# ZeeSoC_v1_0.net
KiCad netlist of a schematic drawn in EAGLE
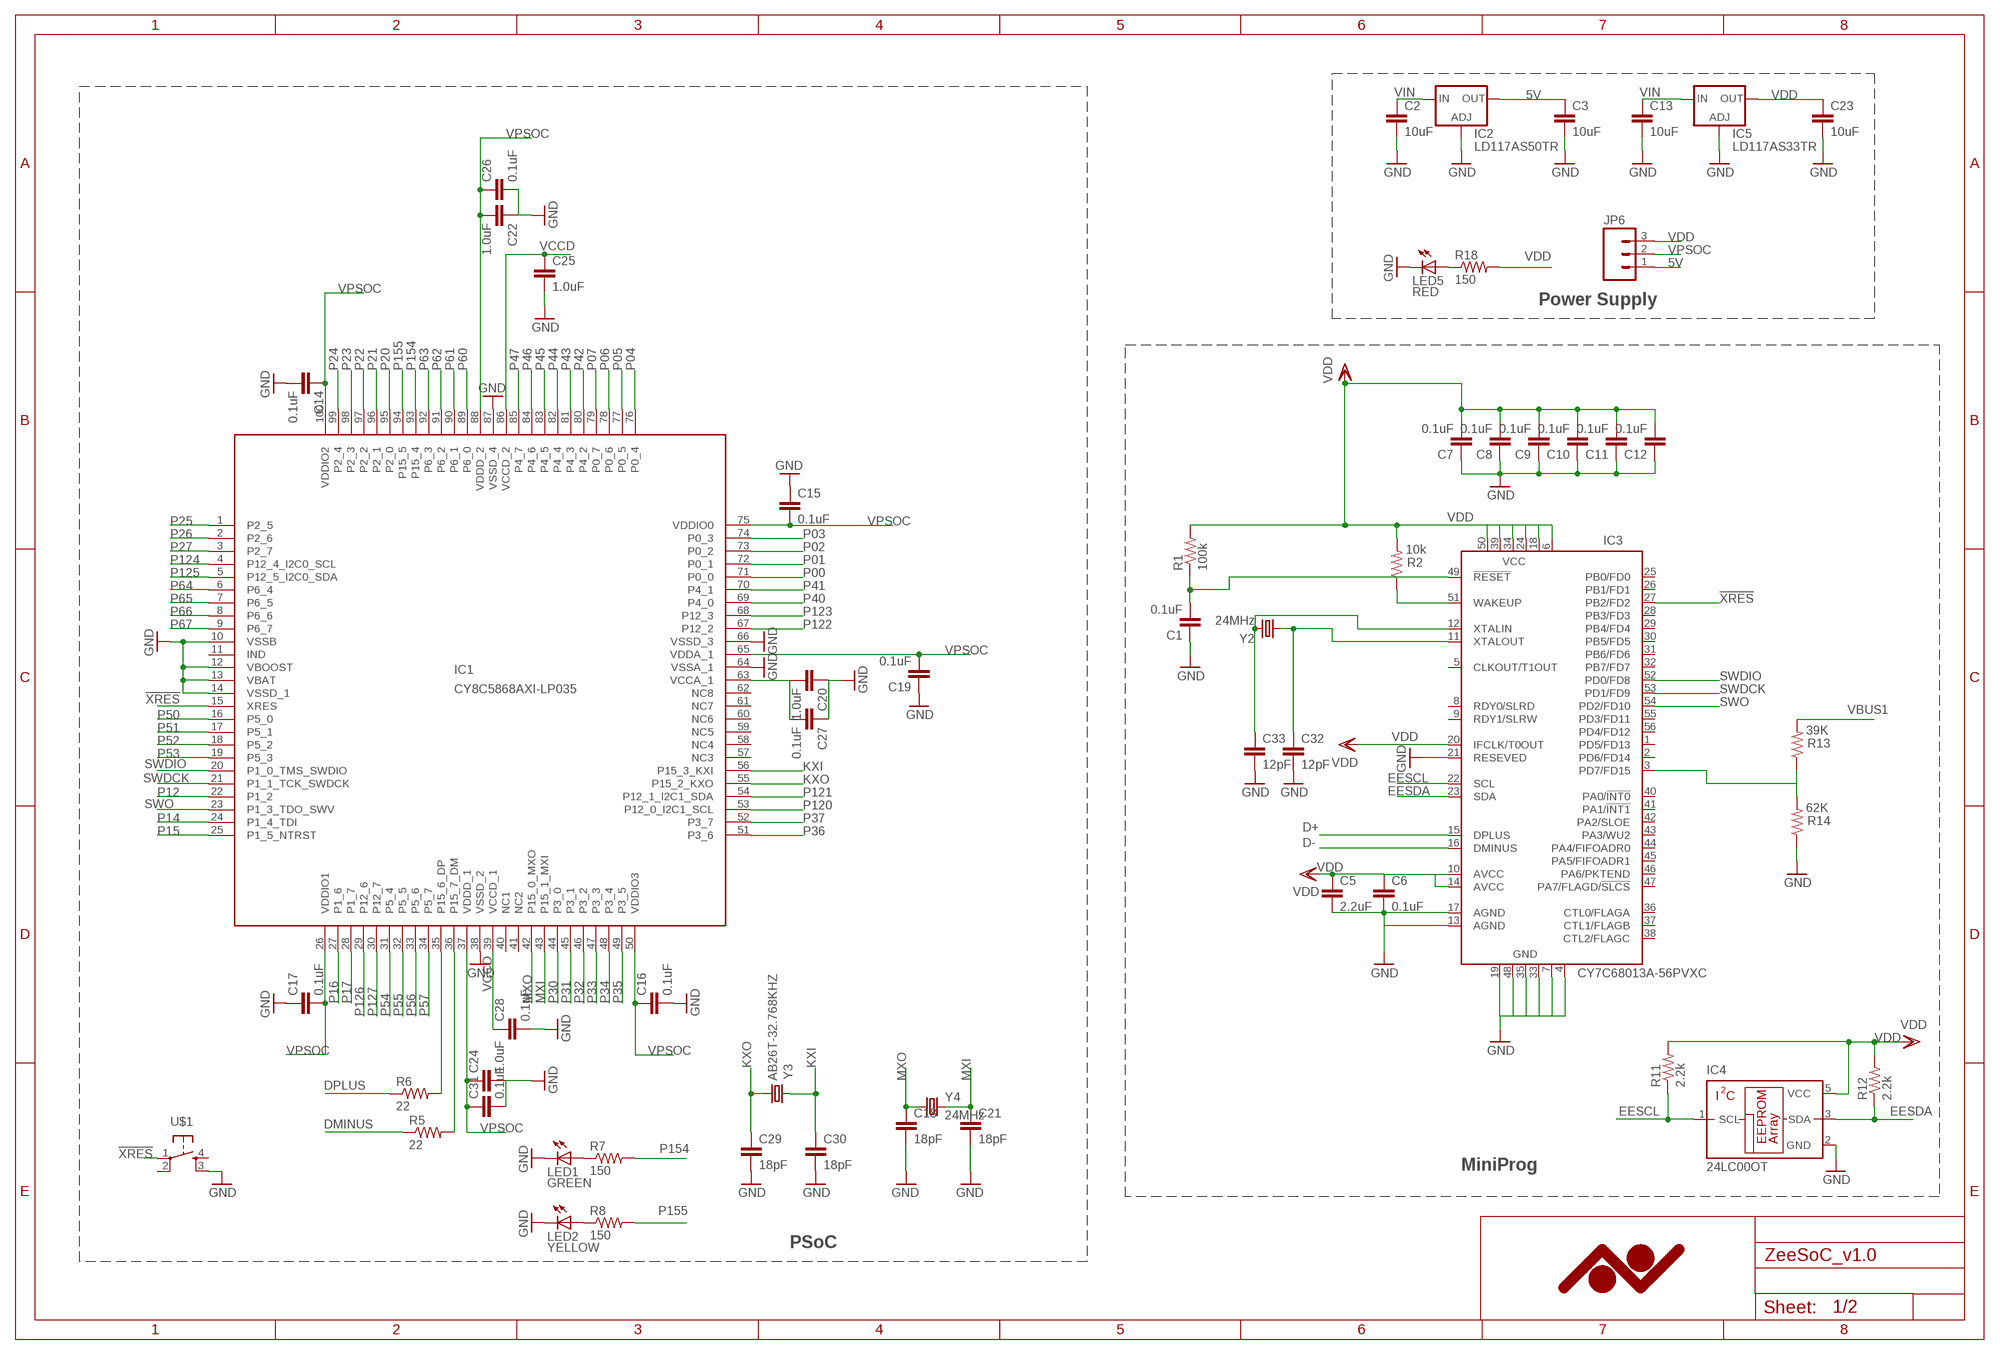
[diagram p0: schematic, sheet 1]
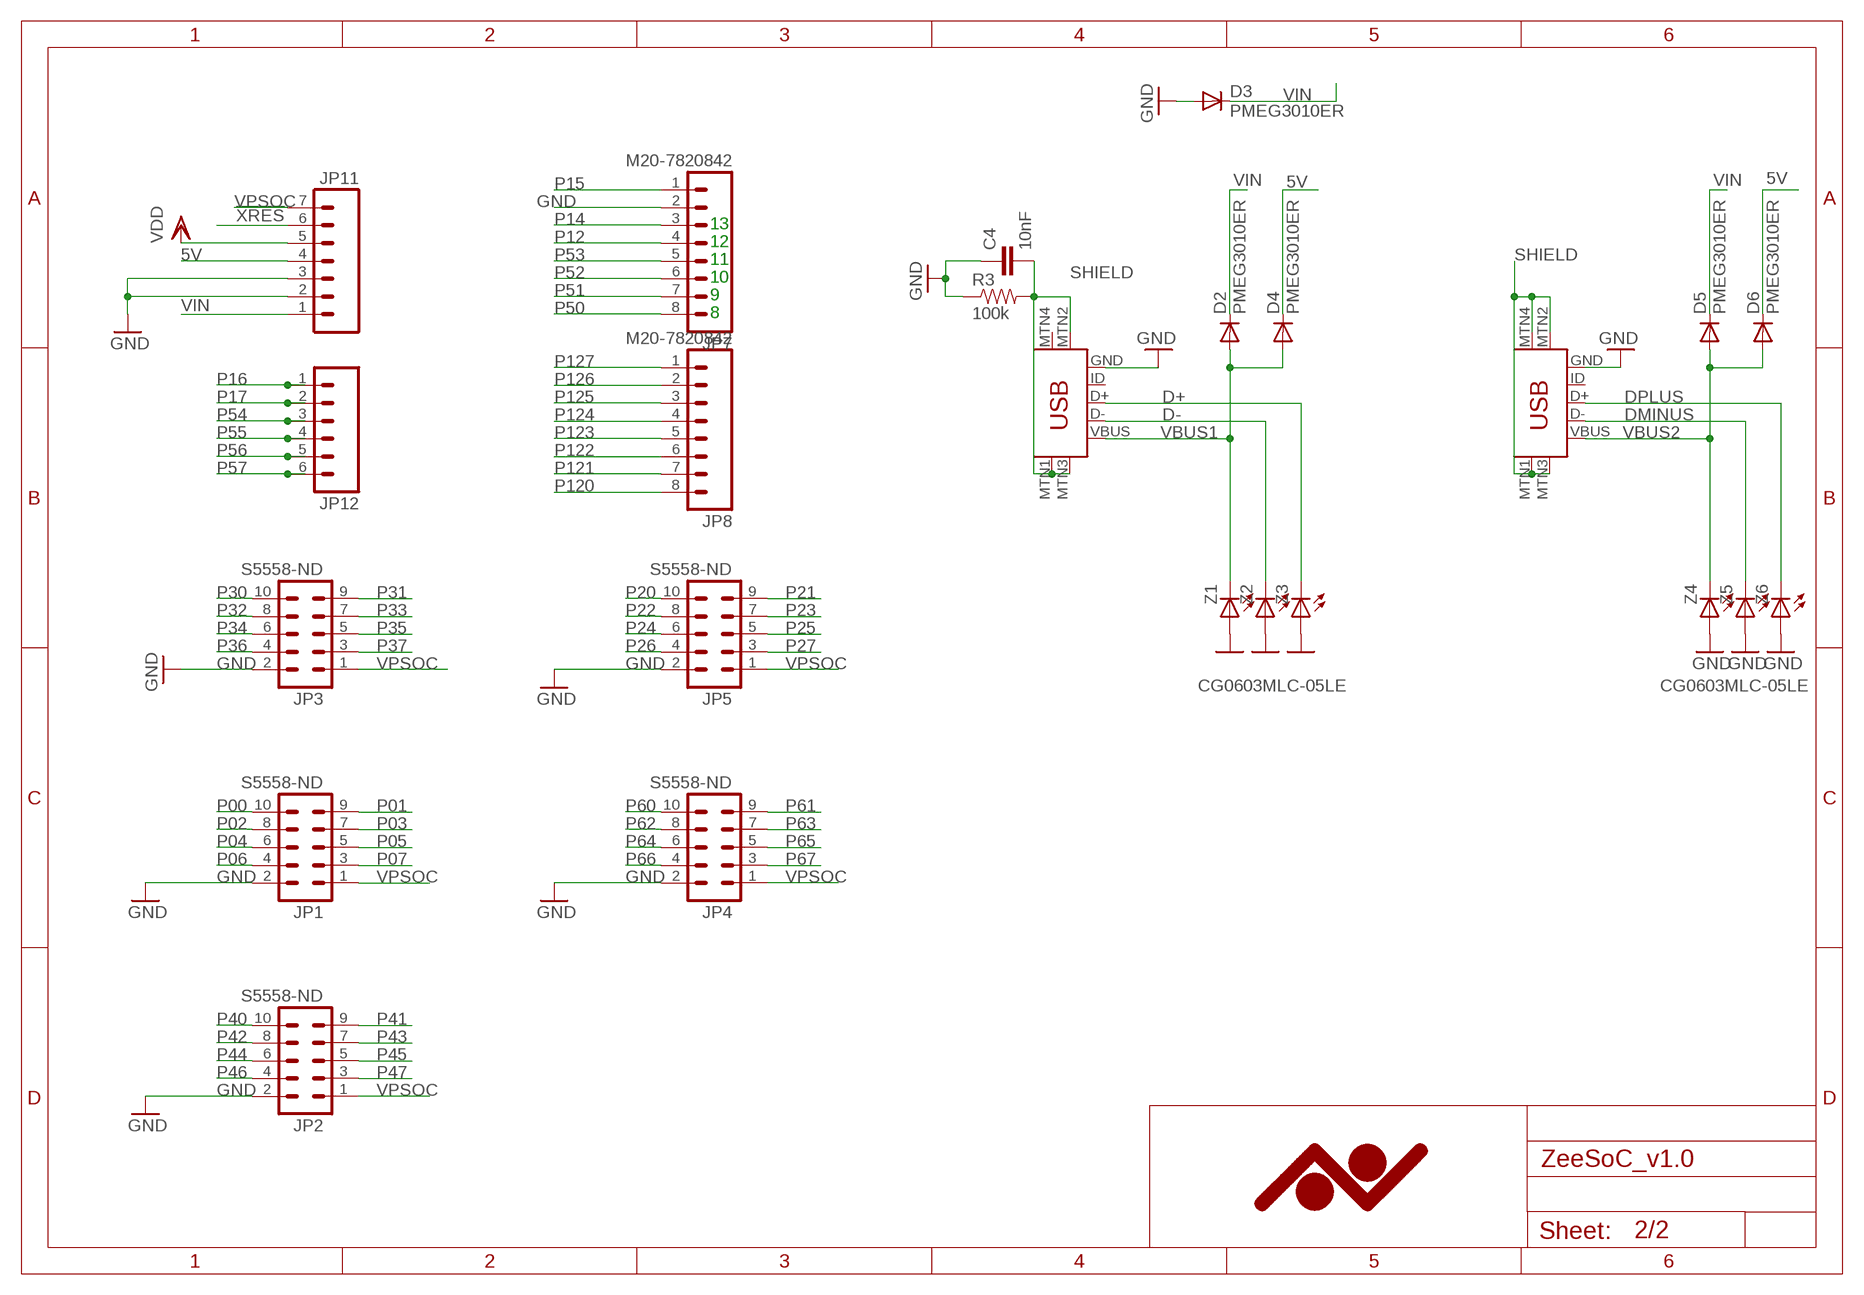
[diagram p1: schematic, sheet 2]

(export (version "E")
  (design (tool "Eeschema 10.0.6"))
  (components
    (comp (ref "C4")
      (value "10nF")
      (footprint "eagle-import:0603-CAP")
      (libsource (lib "eagle-import") (part "SparkFun-Capacitors_CAP0603-CAP"))
    )
    (comp (ref "D2")
      (value "PMEG3010ER")
      (footprint "eagle-import:SOD123")
      (libsource (lib "eagle-import") (part "DIODE-SOD123"))
    )
    (comp (ref "D3")
      (value "PMEG3010ER")
      (footprint "eagle-import:SOD123")
      (libsource (lib "eagle-import") (part "DIODE-SOD123"))
    )
    (comp (ref "D4")
      (value "PMEG3010ER")
      (footprint "eagle-import:SOD123")
      (libsource (lib "eagle-import") (part "DIODE-SOD123"))
    )
    (comp (ref "D5")
      (value "PMEG3010ER")
      (footprint "eagle-import:SOD123")
      (libsource (lib "eagle-import") (part "DIODE-SOD123"))
    )
    (comp (ref "D6")
      (value "PMEG3010ER")
      (footprint "eagle-import:SOD123")
      (libsource (lib "eagle-import") (part "DIODE-SOD123"))
    )
    (comp (ref "JP1")
      (value "S5558-ND")
      (footprint "eagle-import:2X5-NS")
      (libsource (lib "eagle-import") (part "M05X2BLANK"))
    )
    (comp (ref "JP2")
      (value "S5558-ND")
      (footprint "eagle-import:2X5-NS")
      (libsource (lib "eagle-import") (part "M05X2BLANK"))
    )
    (comp (ref "JP3")
      (value "S5558-ND")
      (footprint "eagle-import:2X5-NS")
      (libsource (lib "eagle-import") (part "M05X2BLANK"))
    )
    (comp (ref "JP4")
      (value "S5558-ND")
      (footprint "eagle-import:2X5-NS")
      (libsource (lib "eagle-import") (part "M05X2BLANK"))
    )
    (comp (ref "JP5")
      (value "S5558-ND")
      (footprint "eagle-import:2X5-NS")
      (libsource (lib "eagle-import") (part "M05X2BLANK"))
    )
    (comp (ref "JP7")
      (value "M20-7820842")
      (footprint "eagle-import:1X08")
      (libsource (lib "eagle-import") (part "M081X08"))
    )
    (comp (ref "JP8")
      (value "M20-7820842")
      (footprint "eagle-import:1X08")
      (libsource (lib "eagle-import") (part "M081X08"))
    )
    (comp (ref "JP11")
      (value "M07")
      (footprint "eagle-import:1X07")
      (libsource (lib "eagle-import") (part "M07"))
    )
    (comp (ref "JP12")
      (value "M06SIP")
      (footprint "eagle-import:1X06")
      (libsource (lib "eagle-import") (part "M06SIP"))
    )
    (comp (ref "R3")
      (value "100k")
      (footprint "eagle-import:0603-RES")
      (libsource (lib "eagle-import") (part "RESISTOR0603"))
    )
    (comp (ref "U$5")
      (value "USB-MINIB-5PIN")
      (footprint "eagle-import:USB-MINIB")
      (libsource (lib "eagle-import") (part "USB-MINIB-5PIN"))
    )
    (comp (ref "U$6")
      (value "USB-MINIB-5PIN")
      (footprint "eagle-import:USB-MINIB")
      (libsource (lib "eagle-import") (part "USB-MINIB-5PIN"))
    )
    (comp (ref "Z1")
      (value "CG0603MLC-05LE")
      (footprint "eagle-import:LED-0603")
      (libsource (lib "eagle-import") (part "LED0603"))
    )
    (comp (ref "Z2")
      (value "CG0603MLC-05LE")
      (footprint "eagle-import:LED-0603")
      (libsource (lib "eagle-import") (part "LED0603"))
    )
    (comp (ref "Z3")
      (value "CG0603MLC-05LE")
      (footprint "eagle-import:LED-0603")
      (libsource (lib "eagle-import") (part "LED0603"))
    )
    (comp (ref "Z4")
      (value "CG0603MLC-05LE")
      (footprint "eagle-import:LED-0603")
      (libsource (lib "eagle-import") (part "LED0603"))
    )
    (comp (ref "Z5")
      (value "CG0603MLC-05LE")
      (footprint "eagle-import:LED-0603")
      (libsource (lib "eagle-import") (part "LED0603"))
    )
    (comp (ref "Z6")
      (value "CG0603MLC-05LE")
      (footprint "eagle-import:LED-0603")
      (libsource (lib "eagle-import") (part "LED0603"))
    )
    (comp (ref "C1")
      (value "0.1uF")
      (footprint "eagle-import:0603-CAP")
      (libsource (lib "eagle-import") (part "SparkFun-Capacitors_CAP0603-CAP"))
    )
    (comp (ref "C2")
      (value "10uF")
      (footprint "eagle-import:0805")
      (libsource (lib "eagle-import") (part "CAP0805"))
    )
    (comp (ref "C3")
      (value "10uF")
      (footprint "eagle-import:0805")
      (libsource (lib "eagle-import") (part "CAP0805"))
    )
    (comp (ref "C5")
      (value "2.2uF")
      (footprint "eagle-import:0805")
      (libsource (lib "eagle-import") (part "SparkFun-Capacitors_CAP0805"))
    )
    (comp (ref "C6")
      (value "0.1uF")
      (footprint "eagle-import:0603-CAP")
      (libsource (lib "eagle-import") (part "SparkFun-Capacitors_CAP0603-CAP"))
    )
    (comp (ref "C7")
      (value "0.1uF")
      (footprint "eagle-import:0603-CAP")
      (libsource (lib "eagle-import") (part "SparkFun-Capacitors_CAP0603-CAP"))
    )
    (comp (ref "C8")
      (value "0.1uF")
      (footprint "eagle-import:0603-CAP")
      (libsource (lib "eagle-import") (part "SparkFun-Capacitors_CAP0603-CAP"))
    )
    (comp (ref "C9")
      (value "0.1uF")
      (footprint "eagle-import:0603-CAP")
      (libsource (lib "eagle-import") (part "SparkFun-Capacitors_CAP0603-CAP"))
    )
    (comp (ref "C10")
      (value "0.1uF")
      (footprint "eagle-import:0603-CAP")
      (libsource (lib "eagle-import") (part "SparkFun-Capacitors_CAP0603-CAP"))
    )
    (comp (ref "C11")
      (value "0.1uF")
      (footprint "eagle-import:0603-CAP")
      (libsource (lib "eagle-import") (part "SparkFun-Capacitors_CAP0603-CAP"))
    )
    (comp (ref "C12")
      (value "0.1uF")
      (footprint "eagle-import:0603-CAP")
      (libsource (lib "eagle-import") (part "SparkFun-Capacitors_CAP0603-CAP"))
    )
    (comp (ref "C13")
      (value "10uF")
      (footprint "eagle-import:0805")
      (libsource (lib "eagle-import") (part "CAP0805"))
    )
    (comp (ref "C14")
      (value "0.1uF")
      (footprint "eagle-import:0603-CAP")
      (libsource (lib "eagle-import") (part "SparkFun-Capacitors_CAP0603-CAP"))
    )
    (comp (ref "C15")
      (value "0.1uF")
      (footprint "eagle-import:0603-CAP")
      (libsource (lib "eagle-import") (part "SparkFun-Capacitors_CAP0603-CAP"))
    )
    (comp (ref "C16")
      (value "0.1uF")
      (footprint "eagle-import:0603-CAP")
      (libsource (lib "eagle-import") (part "SparkFun-Capacitors_CAP0603-CAP"))
    )
    (comp (ref "C17")
      (value "0.1uF")
      (footprint "eagle-import:0603-CAP")
      (libsource (lib "eagle-import") (part "SparkFun-Capacitors_CAP0603-CAP"))
    )
    (comp (ref "C18")
      (value "18pF")
      (footprint "eagle-import:0603-CAP")
      (libsource (lib "eagle-import") (part "SparkFun-Capacitors_CAP0603-CAP"))
    )
    (comp (ref "C19")
      (value "0.1uF")
      (footprint "eagle-import:0603-CAP")
      (libsource (lib "eagle-import") (part "SparkFun-Capacitors_CAP0603-CAP"))
    )
    (comp (ref "C20")
      (value "1.0uF")
      (footprint "eagle-import:0603-CAP")
      (libsource (lib "eagle-import") (part "SparkFun-Capacitors_CAP0603-CAP"))
    )
    (comp (ref "C21")
      (value "18pF")
      (footprint "eagle-import:0603-CAP")
      (libsource (lib "eagle-import") (part "SparkFun-Capacitors_CAP0603-CAP"))
    )
    (comp (ref "C22")
      (value "1.0uF")
      (footprint "eagle-import:0603-CAP")
      (libsource (lib "eagle-import") (part "SparkFun-Capacitors_CAP0603-CAP"))
    )
    (comp (ref "C23")
      (value "10uF")
      (footprint "eagle-import:0805")
      (libsource (lib "eagle-import") (part "CAP0805"))
    )
    (comp (ref "C24")
      (value "1.0uF")
      (footprint "eagle-import:0603-CAP")
      (libsource (lib "eagle-import") (part "SparkFun-Capacitors_CAP0603-CAP"))
    )
    (comp (ref "C25")
      (value "1.0uF")
      (footprint "eagle-import:0603-CAP")
      (libsource (lib "eagle-import") (part "SparkFun-Capacitors_CAP0603-CAP"))
    )
    (comp (ref "C26")
      (value "0.1uF")
      (footprint "eagle-import:0603-CAP")
      (libsource (lib "eagle-import") (part "SparkFun-Capacitors_CAP0603-CAP"))
    )
    (comp (ref "C27")
      (value "0.1uF")
      (footprint "eagle-import:0603-CAP")
      (libsource (lib "eagle-import") (part "SparkFun-Capacitors_CAP0603-CAP"))
    )
    (comp (ref "C28")
      (value "0.1uF")
      (footprint "eagle-import:0603-CAP")
      (libsource (lib "eagle-import") (part "SparkFun-Capacitors_CAP0603-CAP"))
    )
    (comp (ref "C29")
      (value "18pF")
      (footprint "eagle-import:0603-CAP")
      (libsource (lib "eagle-import") (part "SparkFun-Capacitors_CAP0603-CAP"))
    )
    (comp (ref "C30")
      (value "18pF")
      (footprint "eagle-import:0603-CAP")
      (libsource (lib "eagle-import") (part "SparkFun-Capacitors_CAP0603-CAP"))
    )
    (comp (ref "C31")
      (value "0.1uF")
      (footprint "eagle-import:0603-CAP")
      (libsource (lib "eagle-import") (part "SparkFun-Capacitors_CAP0603-CAP"))
    )
    (comp (ref "C32")
      (value "12pF")
      (footprint "eagle-import:0603-CAP")
      (libsource (lib "eagle-import") (part "SparkFun-Capacitors_CAP0603-CAP"))
    )
    (comp (ref "C33")
      (value "12pF")
      (footprint "eagle-import:0603-CAP")
      (libsource (lib "eagle-import") (part "SparkFun-Capacitors_CAP0603-CAP"))
    )
    (comp (ref "IC1")
      (value "CY8C5868AXI-LP035")
      (footprint "eagle-import:TQFP-100")
      (libsource (lib "eagle-import") (part "CY8C3X66AXI"))
    )
    (comp (ref "IC2")
      (value "LD117AS50TR")
      (footprint "eagle-import:SOT223")
      (libsource (lib "eagle-import") (part "LD117A?S50TR"))
    )
    (comp (ref "IC3")
      (value "CY7C68013A-56PVXC")
      (footprint "eagle-import:SSOP56")
      (fields (field (name "MF") "CYPRESS SEMICONDUCTOR CORPORAT"))
      (libsource (lib "eagle-import") (part "CY7C6801A-56PVXC3"))
    )
    (comp (ref "IC4")
      (value "24LC00OT")
      (footprint "eagle-import:SOT23-5L")
      (libsource (lib "eagle-import") (part "2400OTLC"))
    )
    (comp (ref "IC5")
      (value "LD117AS33TR")
      (footprint "eagle-import:SOT223")
      (libsource (lib "eagle-import") (part "LD117A?S33TR"))
    )
    (comp (ref "JP6")
      (value "M03PTH")
      (footprint "eagle-import:1X03")
      (libsource (lib "eagle-import") (part "M03PTH"))
    )
    (comp (ref "LED1")
      (value "GREEN")
      (footprint "eagle-import:LED-0603")
      (libsource (lib "eagle-import") (part "LED0603"))
    )
    (comp (ref "LED2")
      (value "YELLOW")
      (footprint "eagle-import:LED-0603")
      (libsource (lib "eagle-import") (part "LED0603"))
    )
    (comp (ref "LED5")
      (value "RED")
      (footprint "eagle-import:LED-0603")
      (libsource (lib "eagle-import") (part "LED0603"))
    )
    (comp (ref "R1")
      (value "100k")
      (footprint "eagle-import:0603-RES")
      (libsource (lib "eagle-import") (part "RESISTOR0603"))
    )
    (comp (ref "R2")
      (value "10k")
      (footprint "eagle-import:0603-RES")
      (libsource (lib "eagle-import") (part "RESISTOR0603"))
    )
    (comp (ref "R5")
      (value "22")
      (footprint "eagle-import:0603-RES")
      (libsource (lib "eagle-import") (part "RESISTOR0603"))
    )
    (comp (ref "R6")
      (value "22")
      (footprint "eagle-import:0603-RES")
      (libsource (lib "eagle-import") (part "RESISTOR0603"))
    )
    (comp (ref "R7")
      (value "150")
      (footprint "eagle-import:0603-RES")
      (libsource (lib "eagle-import") (part "RESISTOR0603-RES"))
    )
    (comp (ref "R8")
      (value "150")
      (footprint "eagle-import:0603-RES")
      (libsource (lib "eagle-import") (part "RESISTOR0603-RES"))
    )
    (comp (ref "R11")
      (value "2.2k")
      (footprint "eagle-import:0603-RES")
      (libsource (lib "eagle-import") (part "RESISTOR0603"))
    )
    (comp (ref "R12")
      (value "2.2k")
      (footprint "eagle-import:0603-RES")
      (libsource (lib "eagle-import") (part "RESISTOR0603"))
    )
    (comp (ref "R13")
      (value "39K")
      (footprint "eagle-import:0603-RES")
      (libsource (lib "eagle-import") (part "RESISTOR0603"))
    )
    (comp (ref "R14")
      (value "62K")
      (footprint "eagle-import:0603-RES")
      (libsource (lib "eagle-import") (part "RESISTOR0603"))
    )
    (comp (ref "R18")
      (value "150")
      (footprint "eagle-import:0603-RES")
      (libsource (lib "eagle-import") (part "RESISTOR0603-RES"))
    )
    (comp (ref "U$1")
      (value "SWITCH_6.8X6.2")
      (footprint "eagle-import:SWITCH_6.8X6.2")
      (libsource (lib "eagle-import") (part "SWITCH_6.8X6.2"))
    )
    (comp (ref "Y2")
      (value "24MHz")
      (footprint "eagle-import:HC49US")
      (libsource (lib "eagle-import") (part "CRYSTALHC49US"))
    )
    (comp (ref "Y3")
      (value "AB26T-32.768KHZ")
      (footprint "eagle-import:CRYSTAL-32KHZ-SMD")
      (libsource (lib "eagle-import") (part "CRYSTAL32-SMD"))
    )
    (comp (ref "Y4")
      (value "24MHz")
      (footprint "eagle-import:HC49US")
      (libsource (lib "eagle-import") (part "CRYSTALHC49US"))
    )
  )
  (nets
    (net (code "1") (name "5V") (class "Default")
      (node (ref "C3") (pin "1") (pinfunction "1_1") (pintype "passive"))
      (node (ref "D4") (pin "C") (pinfunction "C_C") (pintype "passive"))
      (node (ref "D6") (pin "C") (pinfunction "C_C") (pintype "passive"))
      (node (ref "IC2") (pin "4") (pinfunction "OUT_4") (pintype "passive"))
      (node (ref "JP11") (pin "4") (pinfunction "4_4") (pintype "passive"))
      (node (ref "JP6") (pin "1") (pinfunction "1_1") (pintype "passive"))
    )
    (net (code "2") (name "D+") (class "Default")
      (node (ref "IC3") (pin "15") (pinfunction "DPLUS_15") (pintype "bidirectional"))
      (node (ref "U$5") (pin "D+") (pinfunction "D+_D+") (pintype "bidirectional"))
      (node (ref "Z3") (pin "C") (pinfunction "C_C") (pintype "passive"))
    )
    (net (code "3") (name "D-") (class "Default")
      (node (ref "IC3") (pin "16") (pinfunction "DMINUS_16") (pintype "bidirectional"))
      (node (ref "U$5") (pin "D-") (pinfunction "D-_D-") (pintype "bidirectional"))
      (node (ref "Z2") (pin "C") (pinfunction "C_C") (pintype "passive"))
    )
    (net (code "4") (name "DMINUS") (class "Default")
      (node (ref "R5") (pin "1") (pinfunction "1_1") (pintype "passive"))
      (node (ref "U$6") (pin "D-") (pinfunction "D-_D-") (pintype "bidirectional"))
      (node (ref "Z5") (pin "C") (pinfunction "C_C") (pintype "passive"))
    )
    (net (code "5") (name "DPLUS") (class "Default")
      (node (ref "R6") (pin "1") (pinfunction "1_1") (pintype "passive"))
      (node (ref "U$6") (pin "D+") (pinfunction "D+_D+") (pintype "bidirectional"))
      (node (ref "Z6") (pin "C") (pinfunction "C_C") (pintype "passive"))
    )
    (net (code "6") (name "EESCL") (class "Default")
      (node (ref "IC3") (pin "22") (pinfunction "SCL_22") (pintype "output"))
      (node (ref "IC4") (pin "1") (pinfunction "SCL_1") (pintype "input"))
      (node (ref "R11") (pin "1") (pinfunction "1_1") (pintype "passive"))
    )
    (net (code "7") (name "EESDA") (class "Default")
      (node (ref "IC3") (pin "23") (pinfunction "SDA_23") (pintype "bidirectional"))
      (node (ref "IC4") (pin "3") (pinfunction "SDA_3") (pintype "bidirectional"))
      (node (ref "R12") (pin "1") (pinfunction "1_1") (pintype "passive"))
    )
    (net (code "8") (name "GND") (class "Default")
      (node (ref "C1") (pin "1") (pinfunction "1_1") (pintype "passive"))
      (node (ref "C10") (pin "1") (pinfunction "1_1") (pintype "passive"))
      (node (ref "C11") (pin "1") (pinfunction "1_1") (pintype "passive"))
      (node (ref "C12") (pin "1") (pinfunction "1_1") (pintype "passive"))
      (node (ref "C13") (pin "2") (pinfunction "2_2") (pintype "passive"))
      (node (ref "C14") (pin "2") (pinfunction "2_2") (pintype "passive"))
      (node (ref "C15") (pin "1") (pinfunction "1_1") (pintype "passive"))
      (node (ref "C16") (pin "2") (pinfunction "2_2") (pintype "passive"))
      (node (ref "C17") (pin "1") (pinfunction "1_1") (pintype "passive"))
      (node (ref "C18") (pin "2") (pinfunction "2_2") (pintype "passive"))
      (node (ref "C19") (pin "1") (pinfunction "1_1") (pintype "passive"))
      (node (ref "C2") (pin "2") (pinfunction "2_2") (pintype "passive"))
      (node (ref "C20") (pin "1") (pinfunction "1_1") (pintype "passive"))
      (node (ref "C21") (pin "2") (pinfunction "2_2") (pintype "passive"))
      (node (ref "C22") (pin "1") (pinfunction "1_1") (pintype "passive"))
      (node (ref "C23") (pin "2") (pinfunction "2_2") (pintype "passive"))
      (node (ref "C24") (pin "2") (pinfunction "2_2") (pintype "passive"))
      (node (ref "C25") (pin "2") (pinfunction "2_2") (pintype "passive"))
      (node (ref "C26") (pin "2") (pinfunction "2_2") (pintype "passive"))
      (node (ref "C27") (pin "1") (pinfunction "1_1") (pintype "passive"))
      (node (ref "C28") (pin "2") (pinfunction "2_2") (pintype "passive"))
      (node (ref "C29") (pin "2") (pinfunction "2_2") (pintype "passive"))
      (node (ref "C3") (pin "2") (pinfunction "2_2") (pintype "passive"))
      (node (ref "C30") (pin "2") (pinfunction "2_2") (pintype "passive"))
      (node (ref "C31") (pin "2") (pinfunction "2_2") (pintype "passive"))
      (node (ref "C32") (pin "2") (pinfunction "2_2") (pintype "passive"))
      (node (ref "C33") (pin "2") (pinfunction "2_2") (pintype "passive"))
      (node (ref "C4") (pin "1") (pinfunction "1_1") (pintype "passive"))
      (node (ref "C5") (pin "2") (pinfunction "2_2") (pintype "passive"))
      (node (ref "C6") (pin "2") (pinfunction "2_2") (pintype "passive"))
      (node (ref "C7") (pin "1") (pinfunction "1_1") (pintype "passive"))
      (node (ref "C8") (pin "1") (pinfunction "1_1") (pintype "passive"))
      (node (ref "C9") (pin "1") (pinfunction "1_1") (pintype "passive"))
      (node (ref "D3") (pin "A") (pinfunction "A_A") (pintype "passive"))
      (node (ref "IC1") (pin "10") (pinfunction "VSSB_10") (pintype "passive"))
      (node (ref "IC1") (pin "12") (pinfunction "VBOOST_12") (pintype "passive"))
      (node (ref "IC1") (pin "13") (pinfunction "VBAT_13") (pintype "passive"))
      (node (ref "IC1") (pin "14") (pinfunction "VSSD_1_14") (pintype "passive"))
      (node (ref "IC1") (pin "38") (pinfunction "VSSD_2_38") (pintype "passive"))
      (node (ref "IC1") (pin "64") (pinfunction "VSSA_1_64") (pintype "passive"))
      (node (ref "IC1") (pin "66") (pinfunction "VSSD_3_66") (pintype "passive"))
      (node (ref "IC1") (pin "87") (pinfunction "VSSD_4_87") (pintype "passive"))
      (node (ref "IC2") (pin "1") (pinfunction "ADJ_1") (pintype "input"))
      (node (ref "IC3") (pin "13") (pinfunction "AGND_13") (pintype "input"))
      (node (ref "IC3") (pin "17") (pinfunction "AGND_17") (pintype "input"))
      (node (ref "IC3") (pin "19") (pinfunction "GND_19") (pintype "input"))
      (node (ref "IC3") (pin "21") (pinfunction "RESEVED_21") (pintype "input"))
      (node (ref "IC3") (pin "33") (pinfunction "GND_33") (pintype "input"))
      (node (ref "IC3") (pin "35") (pinfunction "GND_35") (pintype "input"))
      (node (ref "IC3") (pin "4") (pinfunction "GND_4") (pintype "input"))
      (node (ref "IC3") (pin "48") (pinfunction "GND_48") (pintype "input"))
      (node (ref "IC3") (pin "7") (pinfunction "GND_7") (pintype "input"))
      (node (ref "IC4") (pin "2") (pinfunction "GND_2") (pintype "power_in"))
      (node (ref "IC5") (pin "1") (pinfunction "ADJ_1") (pintype "input"))
      (node (ref "JP1") (pin "2") (pinfunction "2_2") (pintype "passive"))
      (node (ref "JP11") (pin "2") (pinfunction "2_2") (pintype "passive"))
      (node (ref "JP11") (pin "3") (pinfunction "3_3") (pintype "passive"))
      (node (ref "JP2") (pin "2") (pinfunction "2_2") (pintype "passive"))
      (node (ref "JP3") (pin "2") (pinfunction "2_2") (pintype "passive"))
      (node (ref "JP4") (pin "2") (pinfunction "2_2") (pintype "passive"))
      (node (ref "JP5") (pin "2") (pinfunction "2_2") (pintype "passive"))
      (node (ref "JP7") (pin "2") (pinfunction "2_2") (pintype "passive"))
      (node (ref "LED1") (pin "C") (pinfunction "C_C") (pintype "passive"))
      (node (ref "LED2") (pin "C") (pinfunction "C_C") (pintype "passive"))
      (node (ref "LED5") (pin "C") (pinfunction "C_C") (pintype "passive"))
      (node (ref "R14") (pin "1") (pinfunction "1_1") (pintype "passive"))
      (node (ref "R3") (pin "1") (pinfunction "1_1") (pintype "passive"))
      (node (ref "U$1") (pin "3") (pinfunction "3_3") (pintype "passive"))
      (node (ref "U$5") (pin "GND") (pinfunction "GND_GND") (pintype "bidirectional"))
      (node (ref "U$6") (pin "GND") (pinfunction "GND_GND") (pintype "bidirectional"))
      (node (ref "Z1") (pin "A") (pinfunction "A_A") (pintype "passive"))
      (node (ref "Z2") (pin "A") (pinfunction "A_A") (pintype "passive"))
      (node (ref "Z3") (pin "A") (pinfunction "A_A") (pintype "passive"))
      (node (ref "Z4") (pin "A") (pinfunction "A_A") (pintype "passive"))
      (node (ref "Z5") (pin "A") (pinfunction "A_A") (pintype "passive"))
      (node (ref "Z6") (pin "A") (pinfunction "A_A") (pintype "passive"))
    )
    (net (code "9") (name "KXI") (class "Default")
      (node (ref "C30") (pin "1") (pinfunction "1_1") (pintype "passive"))
      (node (ref "IC1") (pin "56") (pinfunction "P15_3_KXI_56") (pintype "passive"))
      (node (ref "Y3") (pin "X1") (pinfunction "1_X1") (pintype "passive"))
    )
    (net (code "10") (name "KXO") (class "Default")
      (node (ref "C29") (pin "1") (pinfunction "1_1") (pintype "passive"))
      (node (ref "IC1") (pin "55") (pinfunction "P15_2_KXO_55") (pintype "passive"))
      (node (ref "Y3") (pin "X2") (pinfunction "2_X2") (pintype "passive"))
    )
    (net (code "11") (name "MXI") (class "Default")
      (node (ref "C21") (pin "1") (pinfunction "1_1") (pintype "passive"))
      (node (ref "IC1") (pin "43") (pinfunction "P15_1_MXI_43") (pintype "passive"))
      (node (ref "Y4") (pin "2") (pinfunction "2_2") (pintype "passive"))
    )
    (net (code "12") (name "MXO") (class "Default")
      (node (ref "C18") (pin "1") (pinfunction "1_1") (pintype "passive"))
      (node (ref "IC1") (pin "42") (pinfunction "P15_0_MXO_42") (pintype "passive"))
      (node (ref "Y4") (pin "1") (pinfunction "1_1") (pintype "passive"))
    )
    (net (code "13") (name "Net-(IC1-P15_6_DP)") (class "Default")
      (node (ref "IC1") (pin "35") (pinfunction "P15_6_DP_35") (pintype "passive"))
      (node (ref "R6") (pin "2") (pinfunction "2_2") (pintype "passive"))
    )
    (net (code "14") (name "Net-(IC1-P15_7_DM)") (class "Default")
      (node (ref "IC1") (pin "36") (pinfunction "P15_7_DM_36") (pintype "passive"))
      (node (ref "R5") (pin "2") (pinfunction "2_2") (pintype "passive"))
    )
    (net (code "15") (name "Net-(IC1-VCCA_1)") (class "Default")
      (node (ref "C20") (pin "2") (pinfunction "2_2") (pintype "passive"))
      (node (ref "C27") (pin "2") (pinfunction "2_2") (pintype "passive"))
      (node (ref "IC1") (pin "63") (pinfunction "VCCA_1_63") (pintype "passive"))
    )
    (net (code "16") (name "Net-(IC3-PD7{slash}FD15)") (class "Default")
      (node (ref "IC3") (pin "3") (pinfunction "PD7/FD15_3") (pintype "bidirectional"))
      (node (ref "R13") (pin "1") (pinfunction "1_1") (pintype "passive"))
      (node (ref "R14") (pin "2") (pinfunction "2_2") (pintype "passive"))
    )
    (net (code "17") (name "Net-(IC3-WAKEUP)") (class "Default")
      (node (ref "IC3") (pin "51") (pinfunction "WAKEUP_51") (pintype "input"))
      (node (ref "R2") (pin "1") (pinfunction "1_1") (pintype "passive"))
    )
    (net (code "18") (name "Net-(IC3-XTALIN)") (class "Default")
      (node (ref "C33") (pin "1") (pinfunction "1_1") (pintype "passive"))
      (node (ref "IC3") (pin "12") (pinfunction "XTALIN_12") (pintype "input"))
      (node (ref "Y2") (pin "2") (pinfunction "2_2") (pintype "passive"))
    )
    (net (code "19") (name "Net-(IC3-XTALOUT)") (class "Default")
      (node (ref "C32") (pin "1") (pinfunction "1_1") (pintype "passive"))
      (node (ref "IC3") (pin "11") (pinfunction "XTALOUT_11") (pintype "input"))
      (node (ref "Y2") (pin "1") (pinfunction "1_1") (pintype "passive"))
    )
    (net (code "20") (name "Net-(IC3-~{RESET})") (class "Default")
      (node (ref "C1") (pin "2") (pinfunction "2_2") (pintype "passive"))
      (node (ref "IC3") (pin "49") (pinfunction "~{RESET}_49") (pintype "input"))
      (node (ref "R1") (pin "1") (pinfunction "1_1") (pintype "passive"))
    )
    (net (code "21") (name "Net-(LED1-PadA)") (class "Default")
      (node (ref "LED1") (pin "A") (pinfunction "A_A") (pintype "passive"))
      (node (ref "R7") (pin "1") (pinfunction "1_1") (pintype "passive"))
    )
    (net (code "22") (name "Net-(LED2-PadA)") (class "Default")
      (node (ref "LED2") (pin "A") (pinfunction "A_A") (pintype "passive"))
      (node (ref "R8") (pin "1") (pinfunction "1_1") (pintype "passive"))
    )
    (net (code "23") (name "Net-(LED5-PadA)") (class "Default")
      (node (ref "LED5") (pin "A") (pinfunction "A_A") (pintype "passive"))
      (node (ref "R18") (pin "1") (pinfunction "1_1") (pintype "passive"))
    )
    (net (code "24") (name "P00") (class "Default")
      (node (ref "IC1") (pin "71") (pinfunction "P0_0_71") (pintype "passive"))
      (node (ref "JP1") (pin "10") (pinfunction "10_10") (pintype "passive"))
    )
    (net (code "25") (name "P01") (class "Default")
      (node (ref "IC1") (pin "72") (pinfunction "P0_1_72") (pintype "passive"))
      (node (ref "JP1") (pin "9") (pinfunction "9_9") (pintype "passive"))
    )
    (net (code "26") (name "P02") (class "Default")
      (node (ref "IC1") (pin "73") (pinfunction "P0_2_73") (pintype "passive"))
      (node (ref "JP1") (pin "8") (pinfunction "8_8") (pintype "passive"))
    )
    (net (code "27") (name "P03") (class "Default")
      (node (ref "IC1") (pin "74") (pinfunction "P0_3_74") (pintype "passive"))
      (node (ref "JP1") (pin "7") (pinfunction "7_7") (pintype "passive"))
    )
    (net (code "28") (name "P04") (class "Default")
      (node (ref "IC1") (pin "76") (pinfunction "P0_4_76") (pintype "passive"))
      (node (ref "JP1") (pin "6") (pinfunction "6_6") (pintype "passive"))
    )
    (net (code "29") (name "P05") (class "Default")
      (node (ref "IC1") (pin "77") (pinfunction "P0_5_77") (pintype "passive"))
      (node (ref "JP1") (pin "5") (pinfunction "5_5") (pintype "passive"))
    )
    (net (code "30") (name "P06") (class "Default")
      (node (ref "IC1") (pin "78") (pinfunction "P0_6_78") (pintype "passive"))
      (node (ref "JP1") (pin "4") (pinfunction "4_4") (pintype "passive"))
    )
    (net (code "31") (name "P07") (class "Default")
      (node (ref "IC1") (pin "79") (pinfunction "P0_7_79") (pintype "passive"))
      (node (ref "JP1") (pin "3") (pinfunction "3_3") (pintype "passive"))
    )
    (net (code "32") (name "P12") (class "Default")
      (node (ref "IC1") (pin "22") (pinfunction "P1_2_22") (pintype "passive"))
      (node (ref "JP7") (pin "4") (pinfunction "4_4") (pintype "passive"))
    )
    (net (code "33") (name "P14") (class "Default")
      (node (ref "IC1") (pin "24") (pinfunction "P1_4_TDI_24") (pintype "passive"))
      (node (ref "JP7") (pin "3") (pinfunction "3_3") (pintype "passive"))
    )
    (net (code "34") (name "P15") (class "Default")
      (node (ref "IC1") (pin "25") (pinfunction "P1_5_NTRST_25") (pintype "passive"))
      (node (ref "JP7") (pin "1") (pinfunction "1_1") (pintype "passive"))
    )
    (net (code "35") (name "P16") (class "Default")
      (node (ref "IC1") (pin "27") (pinfunction "P1_6_27") (pintype "passive"))
      (node (ref "JP12") (pin "1") (pinfunction "1_1") (pintype "passive"))
    )
    (net (code "36") (name "P17") (class "Default")
      (node (ref "IC1") (pin "28") (pinfunction "P1_7_28") (pintype "passive"))
      (node (ref "JP12") (pin "2") (pinfunction "2_2") (pintype "passive"))
    )
    (net (code "37") (name "P20") (class "Default")
      (node (ref "IC1") (pin "95") (pinfunction "P2_0_95") (pintype "passive"))
      (node (ref "JP5") (pin "10") (pinfunction "10_10") (pintype "passive"))
    )
    (net (code "38") (name "P21") (class "Default")
      (node (ref "IC1") (pin "96") (pinfunction "P2_1_96") (pintype "passive"))
      (node (ref "JP5") (pin "9") (pinfunction "9_9") (pintype "passive"))
    )
    (net (code "39") (name "P22") (class "Default")
      (node (ref "IC1") (pin "97") (pinfunction "P2_2_97") (pintype "passive"))
      (node (ref "JP5") (pin "8") (pinfunction "8_8") (pintype "passive"))
    )
    (net (code "40") (name "P23") (class "Default")
      (node (ref "IC1") (pin "98") (pinfunction "P2_3_98") (pintype "passive"))
      (node (ref "JP5") (pin "7") (pinfunction "7_7") (pintype "passive"))
    )
    (net (code "41") (name "P24") (class "Default")
      (node (ref "IC1") (pin "99") (pinfunction "P2_4_99") (pintype "passive"))
      (node (ref "JP5") (pin "6") (pinfunction "6_6") (pintype "passive"))
    )
    (net (code "42") (name "P25") (class "Default")
      (node (ref "IC1") (pin "1") (pinfunction "P2_5_1") (pintype "passive"))
      (node (ref "JP5") (pin "5") (pinfunction "5_5") (pintype "passive"))
    )
    (net (code "43") (name "P26") (class "Default")
      (node (ref "IC1") (pin "2") (pinfunction "P2_6_2") (pintype "passive"))
      (node (ref "JP5") (pin "4") (pinfunction "4_4") (pintype "passive"))
    )
    (net (code "44") (name "P27") (class "Default")
      (node (ref "IC1") (pin "3") (pinfunction "P2_7_3") (pintype "passive"))
      (node (ref "JP5") (pin "3") (pinfunction "3_3") (pintype "passive"))
    )
    (net (code "45") (name "P30") (class "Default")
      (node (ref "IC1") (pin "44") (pinfunction "P3_0_44") (pintype "passive"))
      (node (ref "JP3") (pin "10") (pinfunction "10_10") (pintype "passive"))
    )
    (net (code "46") (name "P31") (class "Default")
      (node (ref "IC1") (pin "45") (pinfunction "P3_1_45") (pintype "passive"))
      (node (ref "JP3") (pin "9") (pinfunction "9_9") (pintype "passive"))
    )
    (net (code "47") (name "P32") (class "Default")
      (node (ref "IC1") (pin "46") (pinfunction "P3_2_46") (pintype "passive"))
      (node (ref "JP3") (pin "8") (pinfunction "8_8") (pintype "passive"))
    )
    (net (code "48") (name "P33") (class "Default")
      (node (ref "IC1") (pin "47") (pinfunction "P3_3_47") (pintype "passive"))
      (node (ref "JP3") (pin "7") (pinfunction "7_7") (pintype "passive"))
    )
    (net (code "49") (name "P34") (class "Default")
      (node (ref "IC1") (pin "48") (pinfunction "P3_4_48") (pintype "passive"))
      (node (ref "JP3") (pin "6") (pinfunction "6_6") (pintype "passive"))
    )
    (net (code "50") (name "P35") (class "Default")
      (node (ref "IC1") (pin "49") (pinfunction "P3_5_49") (pintype "passive"))
      (node (ref "JP3") (pin "5") (pinfunction "5_5") (pintype "passive"))
    )
    (net (code "51") (name "P36") (class "Default")
      (node (ref "IC1") (pin "51") (pinfunction "P3_6_51") (pintype "passive"))
      (node (ref "JP3") (pin "4") (pinfunction "4_4") (pintype "passive"))
    )
    (net (code "52") (name "P37") (class "Default")
      (node (ref "IC1") (pin "52") (pinfunction "P3_7_52") (pintype "passive"))
      (node (ref "JP3") (pin "3") (pinfunction "3_3") (pintype "passive"))
    )
    (net (code "53") (name "P40") (class "Default")
      (node (ref "IC1") (pin "69") (pinfunction "P4_0_69") (pintype "passive"))
      (node (ref "JP2") (pin "10") (pinfunction "10_10") (pintype "passive"))
    )
    (net (code "54") (name "P41") (class "Default")
      (node (ref "IC1") (pin "70") (pinfunction "P4_1_70") (pintype "passive"))
      (node (ref "JP2") (pin "9") (pinfunction "9_9") (pintype "passive"))
    )
    (net (code "55") (name "P42") (class "Default")
      (node (ref "IC1") (pin "80") (pinfunction "P4_2_80") (pintype "passive"))
      (node (ref "JP2") (pin "8") (pinfunction "8_8") (pintype "passive"))
    )
    (net (code "56") (name "P43") (class "Default")
      (node (ref "IC1") (pin "81") (pinfunction "P4_3_81") (pintype "passive"))
      (node (ref "JP2") (pin "7") (pinfunction "7_7") (pintype "passive"))
    )
    (net (code "57") (name "P44") (class "Default")
      (node (ref "IC1") (pin "82") (pinfunction "P4_4_82") (pintype "passive"))
      (node (ref "JP2") (pin "6") (pinfunction "6_6") (pintype "passive"))
    )
    (net (code "58") (name "P45") (class "Default")
      (node (ref "IC1") (pin "83") (pinfunction "P4_5_83") (pintype "passive"))
      (node (ref "JP2") (pin "5") (pinfunction "5_5") (pintype "passive"))
    )
    (net (code "59") (name "P46") (class "Default")
      (node (ref "IC1") (pin "84") (pinfunction "P4_6_84") (pintype "passive"))
      (node (ref "JP2") (pin "4") (pinfunction "4_4") (pintype "passive"))
    )
    (net (code "60") (name "P47") (class "Default")
      (node (ref "IC1") (pin "85") (pinfunction "P4_7_85") (pintype "passive"))
      (node (ref "JP2") (pin "3") (pinfunction "3_3") (pintype "passive"))
    )
    (net (code "61") (name "P50") (class "Default")
      (node (ref "IC1") (pin "16") (pinfunction "P5_0_16") (pintype "passive"))
      (node (ref "JP7") (pin "8") (pinfunction "8_8") (pintype "passive"))
    )
    (net (code "62") (name "P51") (class "Default")
      (node (ref "IC1") (pin "17") (pinfunction "P5_1_17") (pintype "passive"))
      (node (ref "JP7") (pin "7") (pinfunction "7_7") (pintype "passive"))
    )
    (net (code "63") (name "P52") (class "Default")
      (node (ref "IC1") (pin "18") (pinfunction "P5_2_18") (pintype "passive"))
      (node (ref "JP7") (pin "6") (pinfunction "6_6") (pintype "passive"))
    )
    (net (code "64") (name "P53") (class "Default")
      (node (ref "IC1") (pin "19") (pinfunction "P5_3_19") (pintype "passive"))
      (node (ref "JP7") (pin "5") (pinfunction "5_5") (pintype "passive"))
    )
    (net (code "65") (name "P54") (class "Default")
      (node (ref "IC1") (pin "31") (pinfunction "P5_4_31") (pintype "passive"))
      (node (ref "JP12") (pin "3") (pinfunction "3_3") (pintype "passive"))
    )
    (net (code "66") (name "P55") (class "Default")
      (node (ref "IC1") (pin "32") (pinfunction "P5_5_32") (pintype "passive"))
      (node (ref "JP12") (pin "4") (pinfunction "4_4") (pintype "passive"))
    )
    (net (code "67") (name "P56") (class "Default")
      (node (ref "IC1") (pin "33") (pinfunction "P5_6_33") (pintype "passive"))
      (node (ref "JP12") (pin "5") (pinfunction "5_5") (pintype "passive"))
    )
    (net (code "68") (name "P57") (class "Default")
      (node (ref "IC1") (pin "34") (pinfunction "P5_7_34") (pintype "passive"))
      (node (ref "JP12") (pin "6") (pinfunction "6_6") (pintype "passive"))
    )
    (net (code "69") (name "P60") (class "Default")
      (node (ref "IC1") (pin "89") (pinfunction "P6_0_89") (pintype "passive"))
      (node (ref "JP4") (pin "10") (pinfunction "10_10") (pintype "passive"))
    )
    (net (code "70") (name "P61") (class "Default")
      (node (ref "IC1") (pin "90") (pinfunction "P6_1_90") (pintype "passive"))
      (node (ref "JP4") (pin "9") (pinfunction "9_9") (pintype "passive"))
    )
    (net (code "71") (name "P62") (class "Default")
      (node (ref "IC1") (pin "91") (pinfunction "P6_2_91") (pintype "passive"))
      (node (ref "JP4") (pin "8") (pinfunction "8_8") (pintype "passive"))
    )
    (net (code "72") (name "P63") (class "Default")
      (node (ref "IC1") (pin "92") (pinfunction "P6_3_92") (pintype "passive"))
      (node (ref "JP4") (pin "7") (pinfunction "7_7") (pintype "passive"))
    )
    (net (code "73") (name "P64") (class "Default")
      (node (ref "IC1") (pin "6") (pinfunction "P6_4_6") (pintype "passive"))
      (node (ref "JP4") (pin "6") (pinfunction "6_6") (pintype "passive"))
    )
    (net (code "74") (name "P65") (class "Default")
      (node (ref "IC1") (pin "7") (pinfunction "P6_5_7") (pintype "passive"))
      (node (ref "JP4") (pin "5") (pinfunction "5_5") (pintype "passive"))
    )
    (net (code "75") (name "P66") (class "Default")
      (node (ref "IC1") (pin "8") (pinfunction "P6_6_8") (pintype "passive"))
      (node (ref "JP4") (pin "4") (pinfunction "4_4") (pintype "passive"))
    )
    (net (code "76") (name "P67") (class "Default")
      (node (ref "IC1") (pin "9") (pinfunction "P6_7_9") (pintype "passive"))
      (node (ref "JP4") (pin "3") (pinfunction "3_3") (pintype "passive"))
    )
    (net (code "77") (name "P120") (class "Default")
      (node (ref "IC1") (pin "53") (pinfunction "P12_0_I2C1_SCL_53") (pintype "passive"))
      (node (ref "JP8") (pin "8") (pinfunction "8_8") (pintype "passive"))
    )
    (net (code "78") (name "P121") (class "Default")
      (node (ref "IC1") (pin "54") (pinfunction "P12_1_I2C1_SDA_54") (pintype "passive"))
      (node (ref "JP8") (pin "7") (pinfunction "7_7") (pintype "passive"))
    )
    (net (code "79") (name "P122") (class "Default")
      (node (ref "IC1") (pin "67") (pinfunction "P12_2_67") (pintype "passive"))
      (node (ref "JP8") (pin "6") (pinfunction "6_6") (pintype "passive"))
    )
    (net (code "80") (name "P123") (class "Default")
      (node (ref "IC1") (pin "68") (pinfunction "P12_3_68") (pintype "passive"))
      (node (ref "JP8") (pin "5") (pinfunction "5_5") (pintype "passive"))
    )
    (net (code "81") (name "P124") (class "Default")
      (node (ref "IC1") (pin "4") (pinfunction "P12_4_I2C0_SCL_4") (pintype "passive"))
      (node (ref "JP8") (pin "4") (pinfunction "4_4") (pintype "passive"))
    )
    (net (code "82") (name "P125") (class "Default")
      (node (ref "IC1") (pin "5") (pinfunction "P12_5_I2C0_SDA_5") (pintype "passive"))
      (node (ref "JP8") (pin "3") (pinfunction "3_3") (pintype "passive"))
    )
    (net (code "83") (name "P126") (class "Default")
      (node (ref "IC1") (pin "29") (pinfunction "P12_6_29") (pintype "passive"))
      (node (ref "JP8") (pin "2") (pinfunction "2_2") (pintype "passive"))
    )
    (net (code "84") (name "P127") (class "Default")
      (node (ref "IC1") (pin "30") (pinfunction "P12_7_30") (pintype "passive"))
      (node (ref "JP8") (pin "1") (pinfunction "1_1") (pintype "passive"))
    )
    (net (code "85") (name "P154") (class "Default")
      (node (ref "IC1") (pin "93") (pinfunction "P15_4_93") (pintype "passive"))
      (node (ref "R7") (pin "2") (pinfunction "2_2") (pintype "passive"))
    )
    (net (code "86") (name "P155") (class "Default")
      (node (ref "IC1") (pin "94") (pinfunction "P15_5_94") (pintype "passive"))
      (node (ref "R8") (pin "2") (pinfunction "2_2") (pintype "passive"))
    )
    (net (code "87") (name "SHIELD") (class "Default")
      (node (ref "C4") (pin "2") (pinfunction "2_2") (pintype "passive"))
      (node (ref "R3") (pin "2") (pinfunction "2_2") (pintype "passive"))
      (node (ref "U$5") (pin "MTN1") (pinfunction "MTN2_MTN1") (pintype "bidirectional"))
      (node (ref "U$5") (pin "MTN2") (pinfunction "MTN3_MTN2") (pintype "bidirectional"))
      (node (ref "U$5") (pin "MTN3") (pinfunction "MTN1_MTN3") (pintype "bidirectional"))
      (node (ref "U$6") (pin "MTN1") (pinfunction "MTN2_MTN1") (pintype "bidirectional"))
      (node (ref "U$6") (pin "MTN2") (pinfunction "MTN3_MTN2") (pintype "bidirectional"))
      (node (ref "U$6") (pin "MTN3") (pinfunction "MTN1_MTN3") (pintype "bidirectional"))
      (node (ref "U$6") (pin "MTN4") (pinfunction "MTN4_MTN4") (pintype "bidirectional"))
    )
    (net (code "88") (name "SWDCK") (class "Default")
      (node (ref "IC1") (pin "21") (pinfunction "P1_1_TCK_SWDCK_21") (pintype "passive"))
      (node (ref "IC3") (pin "53") (pinfunction "PD1/FD9_53") (pintype "bidirectional"))
    )
    (net (code "89") (name "SWDIO") (class "Default")
      (node (ref "IC1") (pin "20") (pinfunction "P1_0_TMS_SWDIO_20") (pintype "passive"))
      (node (ref "IC3") (pin "52") (pinfunction "PD0/FD8_52") (pintype "bidirectional"))
    )
    (net (code "90") (name "SWO") (class "Default")
      (node (ref "IC1") (pin "23") (pinfunction "P1_3_TDO_SWV_23") (pintype "passive"))
      (node (ref "IC3") (pin "54") (pinfunction "PD2/FD10_54") (pintype "bidirectional"))
    )
    (net (code "91") (name "VBUS1") (class "Default")
      (node (ref "D2") (pin "A") (pinfunction "A_A") (pintype "passive"))
      (node (ref "D4") (pin "A") (pinfunction "A_A") (pintype "passive"))
      (node (ref "R13") (pin "2") (pinfunction "2_2") (pintype "passive"))
      (node (ref "U$5") (pin "VBUS") (pinfunction "VBUS_VBUS") (pintype "bidirectional"))
      (node (ref "Z1") (pin "C") (pinfunction "C_C") (pintype "passive"))
    )
    (net (code "92") (name "VBUS2") (class "Default")
      (node (ref "D5") (pin "A") (pinfunction "A_A") (pintype "passive"))
      (node (ref "D6") (pin "A") (pinfunction "A_A") (pintype "passive"))
      (node (ref "U$6") (pin "VBUS") (pinfunction "VBUS_VBUS") (pintype "bidirectional"))
      (node (ref "Z4") (pin "C") (pinfunction "C_C") (pintype "passive"))
    )
    (net (code "93") (name "VCCD") (class "Default")
      (node (ref "C25") (pin "1") (pinfunction "1_1") (pintype "passive"))
      (node (ref "C28") (pin "1") (pinfunction "1_1") (pintype "passive"))
      (node (ref "IC1") (pin "39") (pinfunction "VCCD_1_39") (pintype "passive"))
      (node (ref "IC1") (pin "86") (pinfunction "VCCD_2_86") (pintype "passive"))
    )
    (net (code "94") (name "VDD") (class "Default")
      (node (ref "C10") (pin "2") (pinfunction "2_2") (pintype "passive"))
      (node (ref "C11") (pin "2") (pinfunction "2_2") (pintype "passive"))
      (node (ref "C12") (pin "2") (pinfunction "2_2") (pintype "passive"))
      (node (ref "C23") (pin "1") (pinfunction "1_1") (pintype "passive"))
      (node (ref "C5") (pin "1") (pinfunction "1_1") (pintype "passive"))
      (node (ref "C6") (pin "1") (pinfunction "1_1") (pintype "passive"))
      (node (ref "C7") (pin "2") (pinfunction "2_2") (pintype "passive"))
      (node (ref "C8") (pin "2") (pinfunction "2_2") (pintype "passive"))
      (node (ref "C9") (pin "2") (pinfunction "2_2") (pintype "passive"))
      (node (ref "IC3") (pin "10") (pinfunction "AVCC_10") (pintype "input"))
      (node (ref "IC3") (pin "14") (pinfunction "AVCC_14") (pintype "input"))
      (node (ref "IC3") (pin "18") (pinfunction "VCC_18") (pintype "input"))
      (node (ref "IC3") (pin "20") (pinfunction "IFCLK/T0OUT_20") (pintype "bidirectional"))
      (node (ref "IC3") (pin "24") (pinfunction "VCC_24") (pintype "input"))
      (node (ref "IC3") (pin "34") (pinfunction "VCC_34") (pintype "input"))
      (node (ref "IC3") (pin "39") (pinfunction "VCC_39") (pintype "input"))
      (node (ref "IC3") (pin "50") (pinfunction "VCC_50") (pintype "input"))
      (node (ref "IC3") (pin "6") (pinfunction "VCC_6") (pintype "input"))
      (node (ref "IC4") (pin "5") (pinfunction "VCC_5") (pintype "power_in"))
      (node (ref "IC5") (pin "4") (pinfunction "OUT_4") (pintype "passive"))
      (node (ref "JP11") (pin "5") (pinfunction "5_5") (pintype "passive"))
      (node (ref "JP6") (pin "3") (pinfunction "3_3") (pintype "passive"))
      (node (ref "R1") (pin "2") (pinfunction "2_2") (pintype "passive"))
      (node (ref "R11") (pin "2") (pinfunction "2_2") (pintype "passive"))
      (node (ref "R12") (pin "2") (pinfunction "2_2") (pintype "passive"))
      (node (ref "R18") (pin "2") (pinfunction "2_2") (pintype "passive"))
      (node (ref "R2") (pin "2") (pinfunction "2_2") (pintype "passive"))
    )
    (net (code "95") (name "VIN") (class "Default")
      (node (ref "C13") (pin "1") (pinfunction "1_1") (pintype "passive"))
      (node (ref "C2") (pin "1") (pinfunction "1_1") (pintype "passive"))
      (node (ref "D2") (pin "C") (pinfunction "C_C") (pintype "passive"))
      (node (ref "D3") (pin "C") (pinfunction "C_C") (pintype "passive"))
      (node (ref "D5") (pin "C") (pinfunction "C_C") (pintype "passive"))
      (node (ref "IC2") (pin "3") (pinfunction "IN_3") (pintype "input"))
      (node (ref "IC5") (pin "3") (pinfunction "IN_3") (pintype "input"))
      (node (ref "JP11") (pin "1") (pinfunction "1_1") (pintype "passive"))
    )
    (net (code "96") (name "VPSOC") (class "Default")
      (node (ref "C14") (pin "1") (pinfunction "1_1") (pintype "passive"))
      (node (ref "C15") (pin "2") (pinfunction "2_2") (pintype "passive"))
      (node (ref "C16") (pin "1") (pinfunction "1_1") (pintype "passive"))
      (node (ref "C17") (pin "2") (pinfunction "2_2") (pintype "passive"))
      (node (ref "C19") (pin "2") (pinfunction "2_2") (pintype "passive"))
      (node (ref "C22") (pin "2") (pinfunction "2_2") (pintype "passive"))
      (node (ref "C24") (pin "1") (pinfunction "1_1") (pintype "passive"))
      (node (ref "C26") (pin "1") (pinfunction "1_1") (pintype "passive"))
      (node (ref "C31") (pin "1") (pinfunction "1_1") (pintype "passive"))
      (node (ref "IC1") (pin "100") (pinfunction "VDDIO2_100") (pintype "passive"))
      (node (ref "IC1") (pin "26") (pinfunction "VDDIO1_26") (pintype "passive"))
      (node (ref "IC1") (pin "37") (pinfunction "VDDD_1_37") (pintype "passive"))
      (node (ref "IC1") (pin "50") (pinfunction "VDDIO3_50") (pintype "passive"))
      (node (ref "IC1") (pin "65") (pinfunction "VDDA_1_65") (pintype "passive"))
      (node (ref "IC1") (pin "75") (pinfunction "VDDIO0_75") (pintype "passive"))
      (node (ref "IC1") (pin "88") (pinfunction "VDDD_2_88") (pintype "passive"))
      (node (ref "JP1") (pin "1") (pinfunction "1_1") (pintype "passive"))
      (node (ref "JP11") (pin "7") (pinfunction "7_7") (pintype "passive"))
      (node (ref "JP2") (pin "1") (pinfunction "1_1") (pintype "passive"))
      (node (ref "JP3") (pin "1") (pinfunction "1_1") (pintype "passive"))
      (node (ref "JP4") (pin "1") (pinfunction "1_1") (pintype "passive"))
      (node (ref "JP5") (pin "1") (pinfunction "1_1") (pintype "passive"))
      (node (ref "JP6") (pin "2") (pinfunction "2_2") (pintype "passive"))
    )
    (net (code "97") (name "unconnected-(IC1-IND-Pad11)") (class "Default")
      (node (ref "IC1") (pin "11") (pinfunction "IND_11") (pintype "passive"))
    )
    (net (code "98") (name "unconnected-(IC1-NC1-Pad40)") (class "Default")
      (node (ref "IC1") (pin "40") (pinfunction "NC1_40") (pintype "passive"))
    )
    (net (code "99") (name "unconnected-(IC1-NC2-Pad41)") (class "Default")
      (node (ref "IC1") (pin "41") (pinfunction "NC2_41") (pintype "passive"))
    )
    (net (code "100") (name "unconnected-(IC1-NC3-Pad57)") (class "Default")
      (node (ref "IC1") (pin "57") (pinfunction "NC3_57") (pintype "passive"))
    )
    (net (code "101") (name "unconnected-(IC1-NC4-Pad58)") (class "Default")
      (node (ref "IC1") (pin "58") (pinfunction "NC4_58") (pintype "passive"))
    )
    (net (code "102") (name "unconnected-(IC1-NC5-Pad59)") (class "Default")
      (node (ref "IC1") (pin "59") (pinfunction "NC5_59") (pintype "passive"))
    )
    (net (code "103") (name "unconnected-(IC1-NC6-Pad60)") (class "Default")
      (node (ref "IC1") (pin "60") (pinfunction "NC6_60") (pintype "passive"))
    )
    (net (code "104") (name "unconnected-(IC1-NC7-Pad61)") (class "Default")
      (node (ref "IC1") (pin "61") (pinfunction "NC7_61") (pintype "passive"))
    )
    (net (code "105") (name "unconnected-(IC1-NC8-Pad62)") (class "Default")
      (node (ref "IC1") (pin "62") (pinfunction "NC8_62") (pintype "passive"))
    )
    (net (code "106") (name "unconnected-(IC3-CLKOUT{slash}T1OUT-Pad5)") (class "Default")
      (node (ref "IC3") (pin "5") (pinfunction "CLKOUT/T1OUT_5") (pintype "input"))
    )
    (net (code "107") (name "unconnected-(IC3-CTL0{slash}FLAGA-Pad36)") (class "Default")
      (node (ref "IC3") (pin "36") (pinfunction "CTL0/FLAGA_36") (pintype "output"))
    )
    (net (code "108") (name "unconnected-(IC3-CTL1{slash}FLAGB-Pad37)") (class "Default")
      (node (ref "IC3") (pin "37") (pinfunction "CTL1/FLAGB_37") (pintype "output"))
    )
    (net (code "109") (name "unconnected-(IC3-CTL2{slash}FLAGC-Pad38)") (class "Default")
      (node (ref "IC3") (pin "38") (pinfunction "CTL2/FLAGC_38") (pintype "output"))
    )
    (net (code "110") (name "unconnected-(IC3-PA0{slash}~{INT0}-Pad40)") (class "Default")
      (node (ref "IC3") (pin "40") (pinfunction "PA0/~{INT0}_40") (pintype "bidirectional"))
    )
    (net (code "111") (name "unconnected-(IC3-PA1{slash}~{INT1}-Pad41)") (class "Default")
      (node (ref "IC3") (pin "41") (pinfunction "PA1/~{INT1}_41") (pintype "bidirectional"))
    )
    (net (code "112") (name "unconnected-(IC3-PA2{slash}SLOE-Pad42)") (class "Default")
      (node (ref "IC3") (pin "42") (pinfunction "PA2/SLOE_42") (pintype "bidirectional"))
    )
    (net (code "113") (name "unconnected-(IC3-PA3{slash}WU2-Pad43)") (class "Default")
      (node (ref "IC3") (pin "43") (pinfunction "PA3/WU2_43") (pintype "bidirectional"))
    )
    (net (code "114") (name "unconnected-(IC3-PA4{slash}FIFOADR0-Pad44)") (class "Default")
      (node (ref "IC3") (pin "44") (pinfunction "PA4/FIFOADR0_44") (pintype "bidirectional"))
    )
    (net (code "115") (name "unconnected-(IC3-PA5{slash}FIFOADR1-Pad45)") (class "Default")
      (node (ref "IC3") (pin "45") (pinfunction "PA5/FIFOADR1_45") (pintype "bidirectional"))
    )
    (net (code "116") (name "unconnected-(IC3-PA6{slash}PKTEND-Pad46)") (class "Default")
      (node (ref "IC3") (pin "46") (pinfunction "PA6/PKTEND_46") (pintype "bidirectional"))
    )
    (net (code "117") (name "unconnected-(IC3-PA7{slash}FLAGD{slash}~{SLCS}-Pad47)") (class "Default")
      (node (ref "IC3") (pin "47") (pinfunction "PA7/FLAGD/~{SLCS}_47") (pintype "bidirectional"))
    )
    (net (code "118") (name "unconnected-(IC3-PB0{slash}FD0-Pad25)") (class "Default")
      (node (ref "IC3") (pin "25") (pinfunction "PB0/FD0_25") (pintype "bidirectional"))
    )
    (net (code "119") (name "unconnected-(IC3-PB1{slash}FD1-Pad26)") (class "Default")
      (node (ref "IC3") (pin "26") (pinfunction "PB1/FD1_26") (pintype "bidirectional"))
    )
    (net (code "120") (name "unconnected-(IC3-PB3{slash}FD3-Pad28)") (class "Default")
      (node (ref "IC3") (pin "28") (pinfunction "PB3/FD3_28") (pintype "bidirectional"))
    )
    (net (code "121") (name "unconnected-(IC3-PB4{slash}FD4-Pad29)") (class "Default")
      (node (ref "IC3") (pin "29") (pinfunction "PB4/FD4_29") (pintype "bidirectional"))
    )
    (net (code "122") (name "unconnected-(IC3-PB5{slash}FD5-Pad30)") (class "Default")
      (node (ref "IC3") (pin "30") (pinfunction "PB5/FD5_30") (pintype "bidirectional"))
    )
    (net (code "123") (name "unconnected-(IC3-PB6{slash}FD6-Pad31)") (class "Default")
      (node (ref "IC3") (pin "31") (pinfunction "PB6/FD6_31") (pintype "bidirectional"))
    )
    (net (code "124") (name "unconnected-(IC3-PB7{slash}FD7-Pad32)") (class "Default")
      (node (ref "IC3") (pin "32") (pinfunction "PB7/FD7_32") (pintype "bidirectional"))
    )
    (net (code "125") (name "unconnected-(IC3-PD3{slash}FD11-Pad55)") (class "Default")
      (node (ref "IC3") (pin "55") (pinfunction "PD3/FD11_55") (pintype "bidirectional"))
    )
    (net (code "126") (name "unconnected-(IC3-PD4{slash}FD12-Pad56)") (class "Default")
      (node (ref "IC3") (pin "56") (pinfunction "PD4/FD12_56") (pintype "bidirectional"))
    )
    (net (code "127") (name "unconnected-(IC3-PD5{slash}FD13-Pad1)") (class "Default")
      (node (ref "IC3") (pin "1") (pinfunction "PD5/FD13_1") (pintype "bidirectional"))
    )
    (net (code "128") (name "unconnected-(IC3-PD6{slash}FD14-Pad2)") (class "Default")
      (node (ref "IC3") (pin "2") (pinfunction "PD6/FD14_2") (pintype "bidirectional"))
    )
    (net (code "129") (name "unconnected-(IC3-RDY0{slash}SLRD-Pad8)") (class "Default")
      (node (ref "IC3") (pin "8") (pinfunction "RDY0/SLRD_8") (pintype "input"))
    )
    (net (code "130") (name "unconnected-(IC3-RDY1{slash}SLRW-Pad9)") (class "Default")
      (node (ref "IC3") (pin "9") (pinfunction "RDY1/SLRW_9") (pintype "input"))
    )
    (net (code "131") (name "unconnected-(U$1-Pad2)") (class "Default")
      (node (ref "U$1") (pin "2") (pinfunction "2_2") (pintype "passive"))
    )
    (net (code "132") (name "unconnected-(U$1-Pad4)") (class "Default")
      (node (ref "U$1") (pin "4") (pinfunction "4_4") (pintype "passive"))
    )
    (net (code "133") (name "unconnected-(U$5-PadID)") (class "Default")
      (node (ref "U$5") (pin "ID") (pinfunction "ID_ID") (pintype "bidirectional"))
    )
    (net (code "134") (name "unconnected-(U$5-PadMTN4)") (class "Default")
      (node (ref "U$5") (pin "MTN4") (pinfunction "MTN4_MTN4") (pintype "bidirectional"))
    )
    (net (code "135") (name "unconnected-(U$6-PadID)") (class "Default")
      (node (ref "U$6") (pin "ID") (pinfunction "ID_ID") (pintype "bidirectional"))
    )
    (net (code "136") (name "~{XRES}") (class "Default")
      (node (ref "IC1") (pin "15") (pinfunction "XRES_15") (pintype "passive"))
      (node (ref "IC3") (pin "27") (pinfunction "PB2/FD2_27") (pintype "bidirectional"))
      (node (ref "JP11") (pin "6") (pinfunction "6_6") (pintype "passive"))
      (node (ref "U$1") (pin "1") (pinfunction "1_1") (pintype "passive"))
    )
  )
)
